# 2025_07_18_fpga.net
KiCad netlist of a schematic drawn in EasyEDA Pro
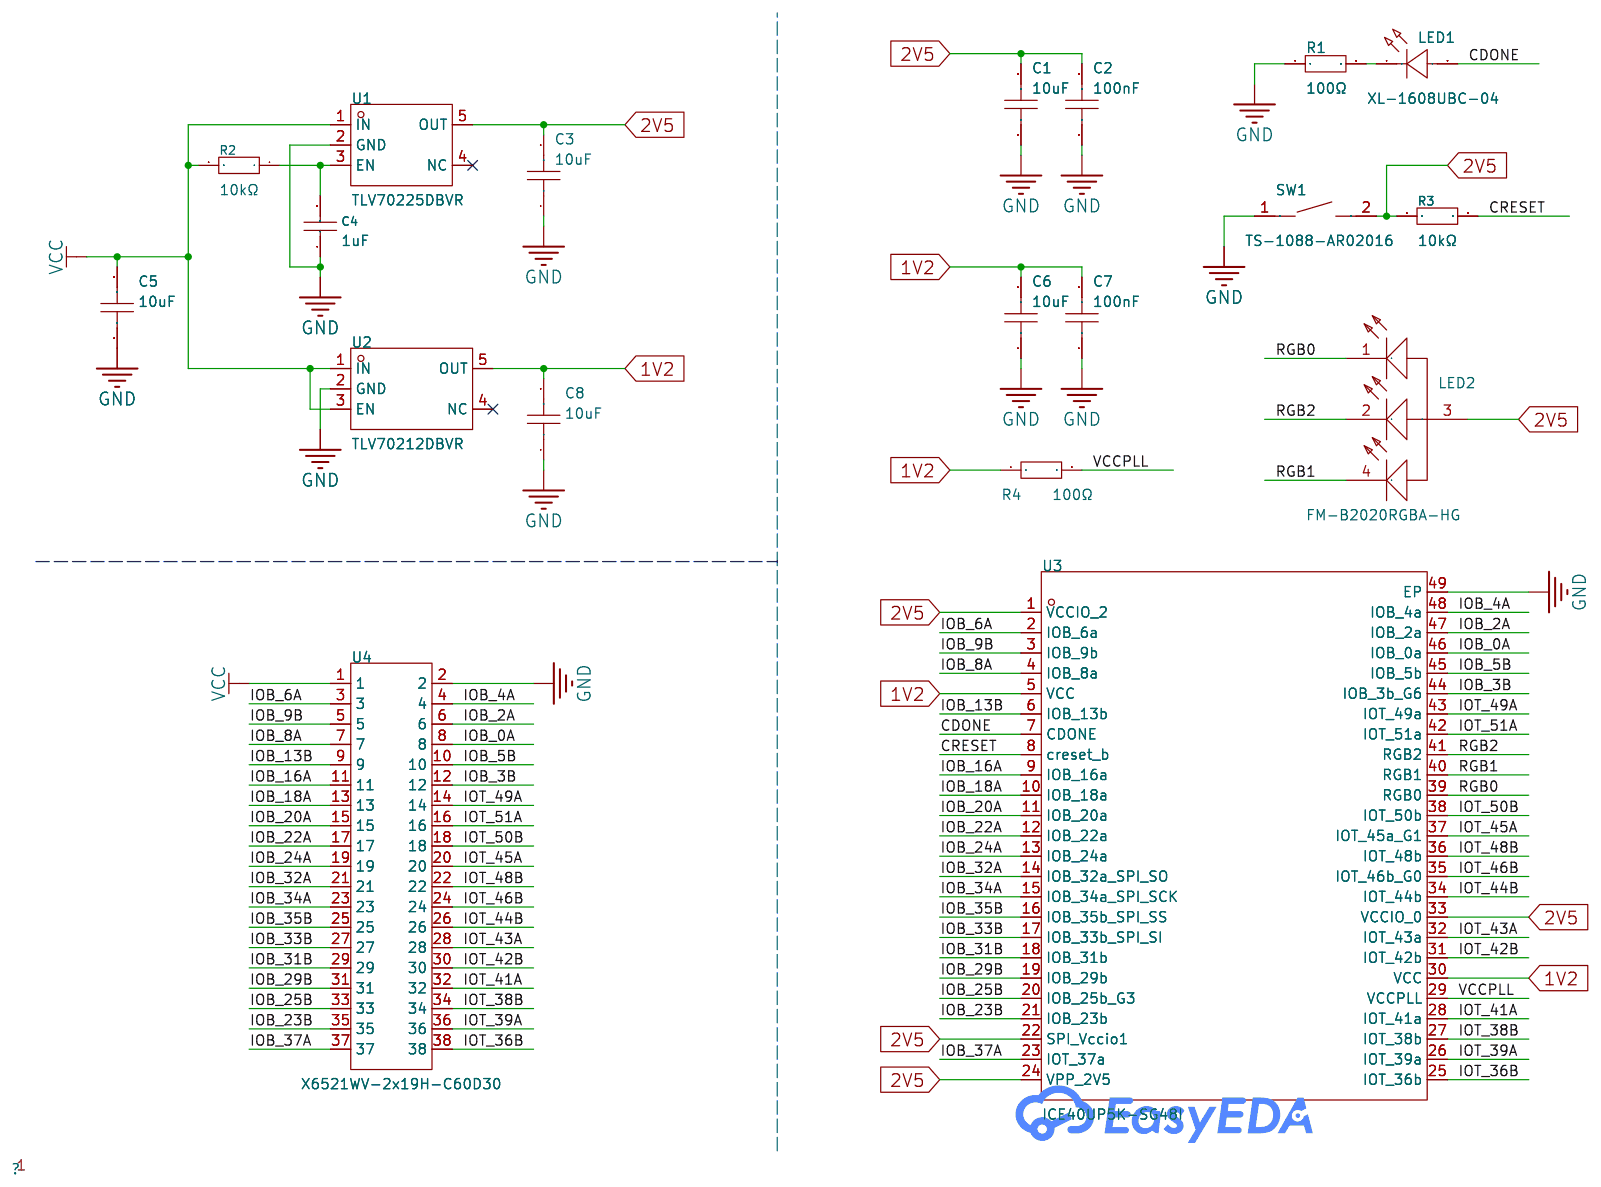
[diagram p0: schematic sheet]

(export (version "E")
  (design (tool "Eeschema 10.0.6"))
  (components
    (comp (ref "C1")
      (value "10uF")
      (footprint "easyedapro:C0402")
      (fields
        (field (name "Manufacturer Part") "CL05A106MP5NUNC")
        (field (name "Manufacturer") "SAMSUNG(三星)")
      )
      (libsource (lib "easyedapro") (part "CL05A106MP5NUNC_C315248"))
    )
    (comp (ref "C2")
      (value "100nF")
      (footprint "easyedapro:C0402")
      (fields
        (field (name "Manufacturer Part") "CL05B104KO5NNNC")
        (field (name "Manufacturer") "SAMSUNG(三星)")
      )
      (libsource (lib "easyedapro") (part "CL05B104KO5NNNC"))
    )
    (comp (ref "C3")
      (value "10uF")
      (footprint "easyedapro:C0402")
      (fields
        (field (name "Manufacturer Part") "CL05A106MP5NUNC")
        (field (name "Manufacturer") "SAMSUNG(三星)")
      )
      (libsource (lib "easyedapro") (part "CL05A106MP5NUNC_C315248"))
    )
    (comp (ref "C4")
      (value "1uF")
      (footprint "easyedapro:C0402")
      (fields
        (field (name "Manufacturer Part") "CL05A105KO5NNNC")
        (field (name "Manufacturer") "SAMSUNG(三星)")
      )
      (libsource (lib "easyedapro") (part "CL05A105KO5NNNC"))
    )
    (comp (ref "C5")
      (value "10uF")
      (footprint "easyedapro:C0402")
      (fields
        (field (name "Manufacturer Part") "CL05A106MP5NUNC")
        (field (name "Manufacturer") "SAMSUNG(三星)")
      )
      (libsource (lib "easyedapro") (part "CL05A106MP5NUNC_C315248"))
    )
    (comp (ref "C6")
      (value "10uF")
      (footprint "easyedapro:C0402")
      (fields
        (field (name "Manufacturer Part") "CL05A106MP5NUNC")
        (field (name "Manufacturer") "SAMSUNG(三星)")
      )
      (libsource (lib "easyedapro") (part "CL05A106MP5NUNC_C315248"))
    )
    (comp (ref "C7")
      (value "100nF")
      (footprint "easyedapro:C0402")
      (fields
        (field (name "Manufacturer Part") "CL05B104KO5NNNC")
        (field (name "Manufacturer") "SAMSUNG(三星)")
      )
      (libsource (lib "easyedapro") (part "CL05B104KO5NNNC"))
    )
    (comp (ref "C8")
      (value "10uF")
      (footprint "easyedapro:C0402")
      (fields
        (field (name "Manufacturer Part") "CL05A106MP5NUNC")
        (field (name "Manufacturer") "SAMSUNG(三星)")
      )
      (libsource (lib "easyedapro") (part "CL05A106MP5NUNC_C315248"))
    )
    (comp (ref "LED1")
      (value "XL-1608UBC-04")
      (footprint "easyedapro:LED0603-RD_BLUE")
      (fields (field (name "Manufacturer") "XINGLIGHT(成兴光)"))
      (libsource (lib "easyedapro") (part "XL-1608UBC-04"))
    )
    (comp (ref "LED2")
      (value "FM-B2020RGBA-HG")
      (footprint "easyedapro:LED-SMD_FM-B2020RGBA-HG")
      (fields (field (name "Manufacturer") "国星光电"))
      (libsource (lib "easyedapro") (part "FM-B2020RGBA-HG"))
    )
    (comp (ref "R1")
      (value "100Ω")
      (footprint "easyedapro:R0402")
      (fields (field (name "Manufacturer Part") "RC0402FR-07100RL") (field (name "Manufacturer") "YAGEO(国巨)"))
      (libsource (lib "easyedapro") (part "RC0402FR-07100RL"))
    )
    (comp (ref "R2")
      (value "10kΩ")
      (footprint "easyedapro:R0402")
      (fields
        (field (name "Manufacturer Part") "0402WGJ0103TCE")
        (field (name "Manufacturer") "UNI-ROYAL(厚声)")
      )
      (libsource (lib "easyedapro") (part "0402WGJ0103TCE"))
    )
    (comp (ref "R3")
      (value "10kΩ")
      (footprint "easyedapro:R0402")
      (fields
        (field (name "Manufacturer Part") "0402WGJ0103TCE")
        (field (name "Manufacturer") "UNI-ROYAL(厚声)")
      )
      (libsource (lib "easyedapro") (part "0402WGJ0103TCE"))
    )
    (comp (ref "R4")
      (value "100Ω")
      (footprint "easyedapro:R0402")
      (fields (field (name "Manufacturer Part") "RC0402FR-07100RL") (field (name "Manufacturer") "YAGEO(国巨)"))
      (libsource (lib "easyedapro") (part "RC0402FR-07100RL"))
    )
    (comp (ref "SW1")
      (value "TS-1088-AR02016")
      (footprint "easyedapro:SW-SMD_L3.9-W3.0-P4.45")
      (fields (field (name "Manufacturer") "XUNPU(讯普)"))
      (libsource (lib "easyedapro") (part "TS-1088-AR02016"))
    )
    (comp (ref "U1")
      (value "TLV70225DBVR")
      (footprint "easyedapro:SOT-23-5_L2.9-W1.6-P0.95-LS2.8-BR")
      (fields (field (name "Manufacturer") "TI(德州仪器)"))
      (libsource (lib "easyedapro") (part "TLV70225DBVR"))
    )
    (comp (ref "U2")
      (value "TLV70212DBVR")
      (footprint "easyedapro:SOT-23-5_L3.0-W1.7-P0.95-LS2.8-BL")
      (fields (field (name "Manufacturer") "TI(德州仪器)"))
      (libsource (lib "easyedapro") (part "TLV70212DBVR"))
    )
    (comp (ref "U3")
      (value "ICE40UP5K-SG48I")
      (footprint "easyedapro:QFN-48_L7.0-W7.0-P0.50-TL-EP5.4-1")
      (fields (field (name "Manufacturer") "LATTICE(莱迪思)"))
      (libsource (lib "easyedapro") (part "ICE40UP5K-SG48I"))
    )
    (comp (ref "U4")
      (value "X6521WV-2x19H-C60D30")
      (footprint "easyedapro:HDR-TH_38P-P2.54-V-M-R2-C19-S2.54")
      (fields (field (name "Manufacturer") "XKB Connection(中国星坤)"))
      (libsource (lib "easyedapro") (part "X6521WV-2X19H-C30D60"))
    )
  )
  (nets
    (net (code "1") (name "/CDONE") (class "Default")
      (node (ref "LED1") (pin "2") (pinfunction "A_2") (pintype "unspecified"))
      (node (ref "U3") (pin "7") (pinfunction "CDONE_7") (pintype "unspecified"))
    )
    (net (code "2") (name "/CRESET") (class "Default")
      (node (ref "R3") (pin "2") (pinfunction "2_2") (pintype "input"))
      (node (ref "U3") (pin "8") (pinfunction "creset_b_8") (pintype "unspecified"))
    )
    (net (code "3") (name "/IOB_0A") (class "Default")
      (node (ref "U3") (pin "46") (pinfunction "IOB_0a_46") (pintype "unspecified"))
      (node (ref "U4") (pin "8") (pinfunction "8_8") (pintype "unspecified"))
    )
    (net (code "4") (name "/IOB_2A") (class "Default")
      (node (ref "U3") (pin "47") (pinfunction "IOB_2a_47") (pintype "unspecified"))
      (node (ref "U4") (pin "6") (pinfunction "6_6") (pintype "unspecified"))
    )
    (net (code "5") (name "/IOB_3B") (class "Default")
      (node (ref "U3") (pin "44") (pinfunction "IOB_3b_G6_44") (pintype "unspecified"))
      (node (ref "U4") (pin "12") (pinfunction "12_12") (pintype "unspecified"))
    )
    (net (code "6") (name "/IOB_4A") (class "Default")
      (node (ref "U3") (pin "48") (pinfunction "IOB_4a_48") (pintype "unspecified"))
      (node (ref "U4") (pin "4") (pinfunction "4_4") (pintype "unspecified"))
    )
    (net (code "7") (name "/IOB_5B") (class "Default")
      (node (ref "U3") (pin "45") (pinfunction "IOB_5b_45") (pintype "unspecified"))
      (node (ref "U4") (pin "10") (pinfunction "10_10") (pintype "unspecified"))
    )
    (net (code "8") (name "/IOB_6A") (class "Default")
      (node (ref "U3") (pin "2") (pinfunction "IOB_6a_2") (pintype "unspecified"))
      (node (ref "U4") (pin "3") (pinfunction "3_3") (pintype "unspecified"))
    )
    (net (code "9") (name "/IOB_8A") (class "Default")
      (node (ref "U3") (pin "4") (pinfunction "IOB_8a_4") (pintype "unspecified"))
      (node (ref "U4") (pin "7") (pinfunction "7_7") (pintype "unspecified"))
    )
    (net (code "10") (name "/IOB_9B") (class "Default")
      (node (ref "U3") (pin "3") (pinfunction "IOB_9b_3") (pintype "unspecified"))
      (node (ref "U4") (pin "5") (pinfunction "5_5") (pintype "unspecified"))
    )
    (net (code "11") (name "/IOB_13B") (class "Default")
      (node (ref "U3") (pin "6") (pinfunction "IOB_13b_6") (pintype "unspecified"))
      (node (ref "U4") (pin "9") (pinfunction "9_9") (pintype "unspecified"))
    )
    (net (code "12") (name "/IOB_16A") (class "Default")
      (node (ref "U3") (pin "9") (pinfunction "IOB_16a_9") (pintype "unspecified"))
      (node (ref "U4") (pin "11") (pinfunction "11_11") (pintype "unspecified"))
    )
    (net (code "13") (name "/IOB_18A") (class "Default")
      (node (ref "U3") (pin "10") (pinfunction "IOB_18a_10") (pintype "unspecified"))
      (node (ref "U4") (pin "13") (pinfunction "13_13") (pintype "unspecified"))
    )
    (net (code "14") (name "/IOB_20A") (class "Default")
      (node (ref "U3") (pin "11") (pinfunction "IOB_20a_11") (pintype "unspecified"))
      (node (ref "U4") (pin "15") (pinfunction "15_15") (pintype "unspecified"))
    )
    (net (code "15") (name "/IOB_22A") (class "Default")
      (node (ref "U3") (pin "12") (pinfunction "IOB_22a_12") (pintype "unspecified"))
      (node (ref "U4") (pin "17") (pinfunction "17_17") (pintype "unspecified"))
    )
    (net (code "16") (name "/IOB_23B") (class "Default")
      (node (ref "U3") (pin "21") (pinfunction "IOB_23b_21") (pintype "unspecified"))
      (node (ref "U4") (pin "35") (pinfunction "35_35") (pintype "unspecified"))
    )
    (net (code "17") (name "/IOB_24A") (class "Default")
      (node (ref "U3") (pin "13") (pinfunction "IOB_24a_13") (pintype "unspecified"))
      (node (ref "U4") (pin "19") (pinfunction "19_19") (pintype "unspecified"))
    )
    (net (code "18") (name "/IOB_25B") (class "Default")
      (node (ref "U3") (pin "20") (pinfunction "IOB_25b_G3_20") (pintype "unspecified"))
      (node (ref "U4") (pin "33") (pinfunction "33_33") (pintype "unspecified"))
    )
    (net (code "19") (name "/IOB_29B") (class "Default")
      (node (ref "U3") (pin "19") (pinfunction "IOB_29b_19") (pintype "unspecified"))
      (node (ref "U4") (pin "31") (pinfunction "31_31") (pintype "unspecified"))
    )
    (net (code "20") (name "/IOB_31B") (class "Default")
      (node (ref "U3") (pin "18") (pinfunction "IOB_31b_18") (pintype "unspecified"))
      (node (ref "U4") (pin "29") (pinfunction "29_29") (pintype "unspecified"))
    )
    (net (code "21") (name "/IOB_32A") (class "Default")
      (node (ref "U3") (pin "14") (pinfunction "IOB_32a_SPI_SO_14") (pintype "unspecified"))
      (node (ref "U4") (pin "21") (pinfunction "21_21") (pintype "unspecified"))
    )
    (net (code "22") (name "/IOB_33B") (class "Default")
      (node (ref "U3") (pin "17") (pinfunction "IOB_33b_SPI_SI_17") (pintype "unspecified"))
      (node (ref "U4") (pin "27") (pinfunction "27_27") (pintype "unspecified"))
    )
    (net (code "23") (name "/IOB_34A") (class "Default")
      (node (ref "U3") (pin "15") (pinfunction "IOB_34a_SPI_SCK_15") (pintype "unspecified"))
      (node (ref "U4") (pin "23") (pinfunction "23_23") (pintype "unspecified"))
    )
    (net (code "24") (name "/IOB_35B") (class "Default")
      (node (ref "U3") (pin "16") (pinfunction "IOB_35b_SPI_SS_16") (pintype "unspecified"))
      (node (ref "U4") (pin "25") (pinfunction "25_25") (pintype "unspecified"))
    )
    (net (code "25") (name "/IOB_37A") (class "Default")
      (node (ref "U3") (pin "23") (pinfunction "IOT_37a_23") (pintype "unspecified"))
      (node (ref "U4") (pin "37") (pinfunction "37_37") (pintype "unspecified"))
    )
    (net (code "26") (name "/IOT_36B") (class "Default")
      (node (ref "U3") (pin "25") (pinfunction "IOT_36b_25") (pintype "unspecified"))
      (node (ref "U4") (pin "38") (pinfunction "38_38") (pintype "unspecified"))
    )
    (net (code "27") (name "/IOT_38B") (class "Default")
      (node (ref "U3") (pin "27") (pinfunction "IOT_38b_27") (pintype "unspecified"))
      (node (ref "U4") (pin "34") (pinfunction "34_34") (pintype "unspecified"))
    )
    (net (code "28") (name "/IOT_39A") (class "Default")
      (node (ref "U3") (pin "26") (pinfunction "IOT_39a_26") (pintype "unspecified"))
      (node (ref "U4") (pin "36") (pinfunction "36_36") (pintype "unspecified"))
    )
    (net (code "29") (name "/IOT_41A") (class "Default")
      (node (ref "U3") (pin "28") (pinfunction "IOT_41a_28") (pintype "unspecified"))
      (node (ref "U4") (pin "32") (pinfunction "32_32") (pintype "unspecified"))
    )
    (net (code "30") (name "/IOT_42B") (class "Default")
      (node (ref "U3") (pin "31") (pinfunction "IOT_42b_31") (pintype "unspecified"))
      (node (ref "U4") (pin "30") (pinfunction "30_30") (pintype "unspecified"))
    )
    (net (code "31") (name "/IOT_43A") (class "Default")
      (node (ref "U3") (pin "32") (pinfunction "IOT_43a_32") (pintype "unspecified"))
      (node (ref "U4") (pin "28") (pinfunction "28_28") (pintype "unspecified"))
    )
    (net (code "32") (name "/IOT_44B") (class "Default")
      (node (ref "U3") (pin "34") (pinfunction "IOT_44b_34") (pintype "unspecified"))
      (node (ref "U4") (pin "26") (pinfunction "26_26") (pintype "unspecified"))
    )
    (net (code "33") (name "/IOT_45A") (class "Default")
      (node (ref "U3") (pin "37") (pinfunction "IOT_45a_G1_37") (pintype "unspecified"))
      (node (ref "U4") (pin "20") (pinfunction "20_20") (pintype "unspecified"))
    )
    (net (code "34") (name "/IOT_46B") (class "Default")
      (node (ref "U3") (pin "35") (pinfunction "IOT_46b_G0_35") (pintype "unspecified"))
      (node (ref "U4") (pin "24") (pinfunction "24_24") (pintype "unspecified"))
    )
    (net (code "35") (name "/IOT_48B") (class "Default")
      (node (ref "U3") (pin "36") (pinfunction "IOT_48b_36") (pintype "unspecified"))
      (node (ref "U4") (pin "22") (pinfunction "22_22") (pintype "unspecified"))
    )
    (net (code "36") (name "/IOT_49A") (class "Default")
      (node (ref "U3") (pin "43") (pinfunction "IOT_49a_43") (pintype "unspecified"))
      (node (ref "U4") (pin "14") (pinfunction "14_14") (pintype "unspecified"))
    )
    (net (code "37") (name "/IOT_50B") (class "Default")
      (node (ref "U3") (pin "38") (pinfunction "IOT_50b_38") (pintype "unspecified"))
      (node (ref "U4") (pin "18") (pinfunction "18_18") (pintype "unspecified"))
    )
    (net (code "38") (name "/IOT_51A") (class "Default")
      (node (ref "U3") (pin "42") (pinfunction "IOT_51a_42") (pintype "unspecified"))
      (node (ref "U4") (pin "16") (pinfunction "16_16") (pintype "unspecified"))
    )
    (net (code "39") (name "/RGB0") (class "Default")
      (node (ref "LED2") (pin "1") (pinfunction "K_1") (pintype "unspecified"))
      (node (ref "U3") (pin "39") (pinfunction "RGB0_39") (pintype "unspecified"))
    )
    (net (code "40") (name "/RGB1") (class "Default")
      (node (ref "LED2") (pin "4") (pinfunction "K_4") (pintype "unspecified"))
      (node (ref "U3") (pin "40") (pinfunction "RGB1_40") (pintype "unspecified"))
    )
    (net (code "41") (name "/RGB2") (class "Default")
      (node (ref "LED2") (pin "2") (pinfunction "K_2") (pintype "unspecified"))
      (node (ref "U3") (pin "41") (pinfunction "RGB2_41") (pintype "unspecified"))
    )
    (net (code "42") (name "/VCCPLL") (class "Default")
      (node (ref "R4") (pin "2") (pinfunction "2_2") (pintype "input"))
      (node (ref "U3") (pin "29") (pinfunction "VCCPLL_29") (pintype "unspecified"))
    )
    (net (code "43") (name "1V2") (class "Default")
      (node (ref "C6") (pin "2") (pinfunction "2_2") (pintype "unspecified"))
      (node (ref "C7") (pin "2") (pinfunction "2_2") (pintype "unspecified"))
      (node (ref "C8") (pin "2") (pinfunction "2_2") (pintype "unspecified"))
      (node (ref "R4") (pin "1") (pinfunction "1_1") (pintype "input"))
      (node (ref "U2") (pin "5") (pinfunction "OUT_5") (pintype "unspecified"))
      (node (ref "U3") (pin "30") (pinfunction "VCC_30") (pintype "unspecified"))
      (node (ref "U3") (pin "5") (pinfunction "VCC_5") (pintype "unspecified"))
    )
    (net (code "44") (name "2V5") (class "Default")
      (node (ref "C1") (pin "2") (pinfunction "2_2") (pintype "unspecified"))
      (node (ref "C2") (pin "2") (pinfunction "2_2") (pintype "unspecified"))
      (node (ref "C3") (pin "2") (pinfunction "2_2") (pintype "unspecified"))
      (node (ref "LED2") (pin "3") (pinfunction "A_3") (pintype "unspecified"))
      (node (ref "R3") (pin "1") (pinfunction "1_1") (pintype "input"))
      (node (ref "SW1") (pin "2") (pinfunction "2_2") (pintype "unspecified"))
      (node (ref "U1") (pin "5") (pinfunction "OUT_5") (pintype "unspecified"))
      (node (ref "U3") (pin "1") (pinfunction "VCCIO_2_1") (pintype "unspecified"))
      (node (ref "U3") (pin "22") (pinfunction "SPI_Vccio1_22") (pintype "unspecified"))
      (node (ref "U3") (pin "24") (pinfunction "VPP_2V5_24") (pintype "unspecified"))
      (node (ref "U3") (pin "33") (pinfunction "VCCIO_0_33") (pintype "unspecified"))
    )
    (net (code "45") (name "GND") (class "Default")
      (node (ref "C1") (pin "1") (pinfunction "1_1") (pintype "unspecified"))
      (node (ref "C2") (pin "1") (pinfunction "1_1") (pintype "unspecified"))
      (node (ref "C3") (pin "1") (pinfunction "1_1") (pintype "unspecified"))
      (node (ref "C4") (pin "1") (pinfunction "1_1") (pintype "input"))
      (node (ref "C5") (pin "1") (pinfunction "1_1") (pintype "unspecified"))
      (node (ref "C6") (pin "1") (pinfunction "1_1") (pintype "unspecified"))
      (node (ref "C7") (pin "1") (pinfunction "1_1") (pintype "unspecified"))
      (node (ref "C8") (pin "1") (pinfunction "1_1") (pintype "unspecified"))
      (node (ref "R1") (pin "1") (pinfunction "1_1") (pintype "input"))
      (node (ref "SW1") (pin "1") (pinfunction "1_1") (pintype "unspecified"))
      (node (ref "U1") (pin "2") (pinfunction "GND_2") (pintype "unspecified"))
      (node (ref "U2") (pin "2") (pinfunction "GND_2") (pintype "unspecified"))
      (node (ref "U3") (pin "49") (pinfunction "EP_49") (pintype "unspecified"))
      (node (ref "U4") (pin "2") (pinfunction "2_2") (pintype "unspecified"))
    )
    (net (code "46") (name "Net-(LED1-K)") (class "Default")
      (node (ref "LED1") (pin "1") (pinfunction "K_1") (pintype "unspecified"))
      (node (ref "R1") (pin "2") (pinfunction "2_2") (pintype "input"))
    )
    (net (code "47") (name "Net-(U1-EN)") (class "Default")
      (node (ref "C4") (pin "2") (pinfunction "2_2") (pintype "input"))
      (node (ref "R2") (pin "1") (pinfunction "1_1") (pintype "input"))
      (node (ref "U1") (pin "3") (pinfunction "EN_3") (pintype "unspecified"))
    )
    (net (code "48") (name "VCC") (class "Default")
      (node (ref "C5") (pin "2") (pinfunction "2_2") (pintype "unspecified"))
      (node (ref "R2") (pin "2") (pinfunction "2_2") (pintype "input"))
      (node (ref "U1") (pin "1") (pinfunction "IN_1") (pintype "unspecified"))
      (node (ref "U2") (pin "1") (pinfunction "IN_1") (pintype "unspecified"))
      (node (ref "U2") (pin "3") (pinfunction "EN_3") (pintype "unspecified"))
      (node (ref "U4") (pin "1") (pinfunction "1_1") (pintype "unspecified"))
    )
    (net (code "49") (name "unconnected-(U1-NC-Pad4)") (class "Default")
      (node (ref "U1") (pin "4") (pinfunction "NC_4") (pintype "unspecified+no_connect"))
    )
    (net (code "50") (name "unconnected-(U2-NC-Pad4)") (class "Default")
      (node (ref "U2") (pin "4") (pinfunction "NC_4") (pintype "unspecified+no_connect"))
    )
  )
)
